# 2021.net
KiCad netlist of a schematic drawn in EasyEDA Pro
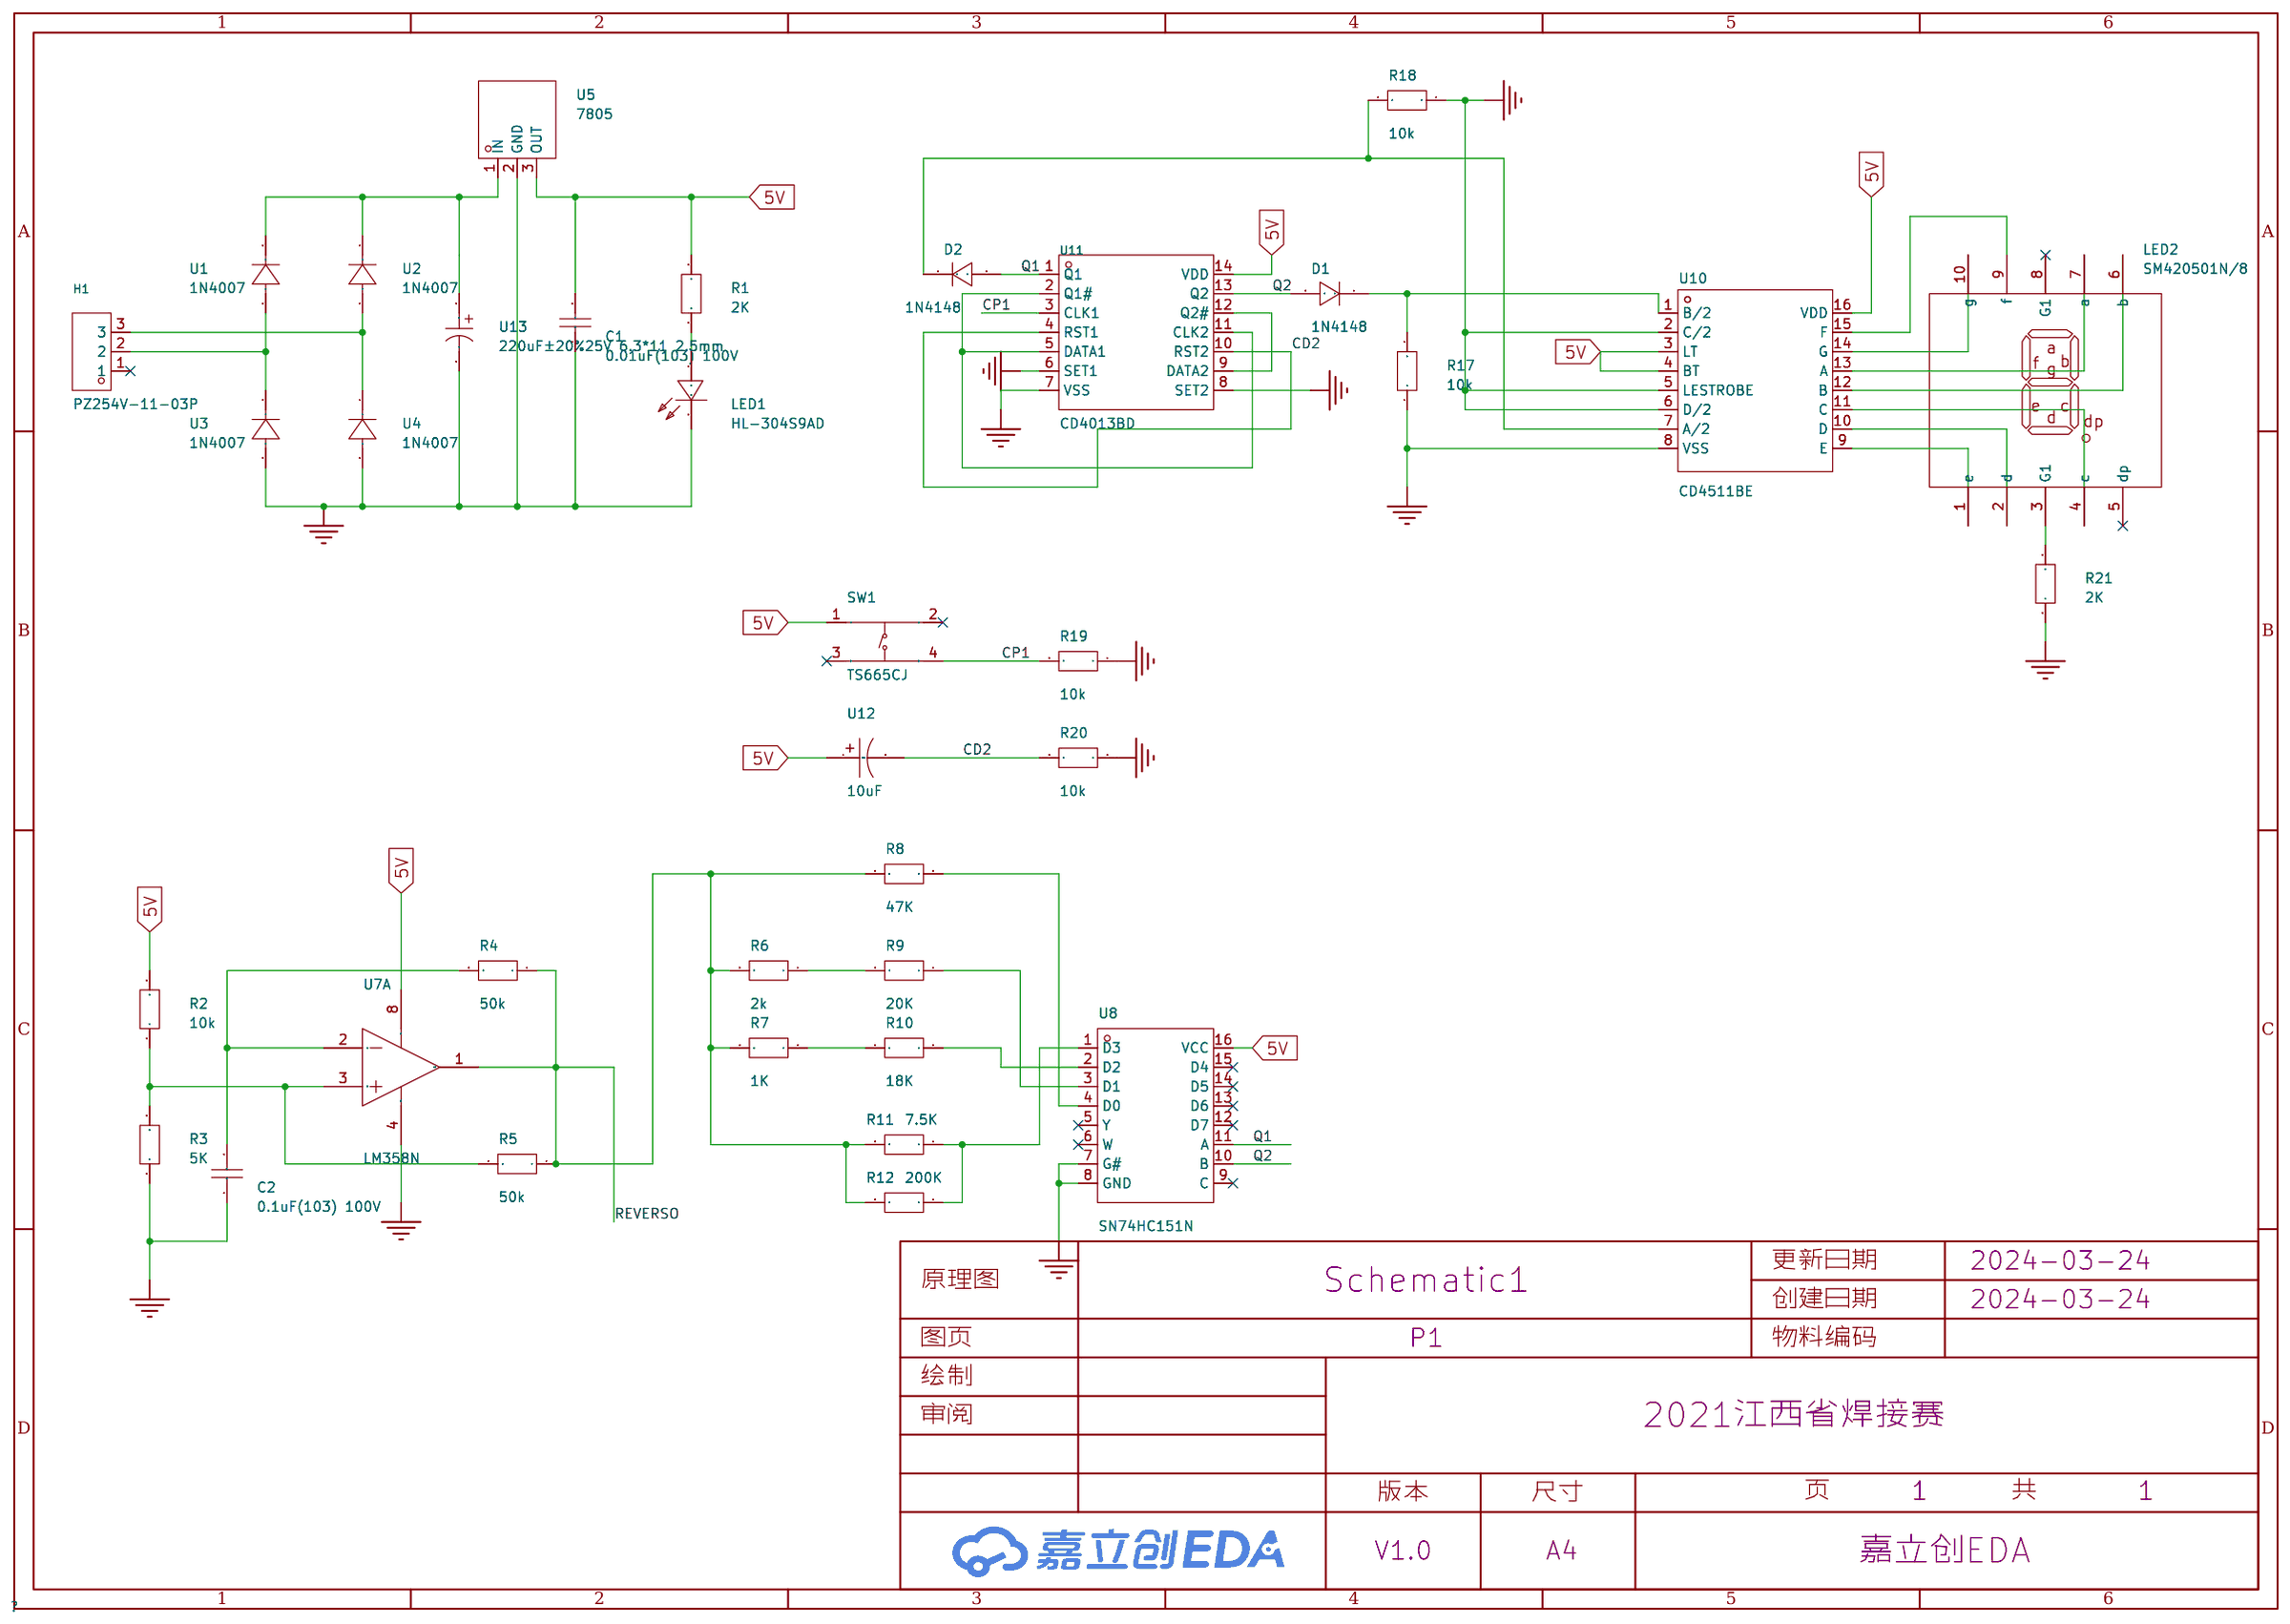
[diagram p0: schematic sheet]

(export (version "E")
  (design (tool "Eeschema 10.0.6"))
  (components
    (comp (ref "C1")
      (value "0.01uF(103) 100V")
      (footprint "easyedapro:CAP-TH_L5.5-W3.0-P5.00-D0.5")
      (libsource (lib "easyedapro") (part "0.01uF(103) 100V"))
    )
    (comp (ref "C2")
      (value "0.1uF(103) 100V")
      (footprint "easyedapro:CAP-TH_L5.5-W3.0-P5.00-D0.5")
      (libsource (lib "easyedapro") (part "0.01uF(103) 100V"))
    )
    (comp (ref "D1")
      (value "1N4148")
      (footprint "easyedapro:DO-35_BD2.0-L4.0-P8.0-D0.5-RD")
      (description "二极管配置:-;正向压降(Vf):-;直流反向耐压(Vr):-;平均整流电流(Io):-;")
      (libsource (lib "easyedapro") (part "1N4148_C13769"))
    )
    (comp (ref "D2")
      (value "1N4148")
      (footprint "easyedapro:DO-35_BD2.0-L4.0-P8.0-D0.5-RD")
      (description "二极管配置:-;正向压降(Vf):-;直流反向耐压(Vr):-;平均整流电流(Io):-;")
      (libsource (lib "easyedapro") (part "1N4148_C13769"))
    )
    (comp (ref "H1")
      (value "PZ254V-11-03P")
      (footprint "easyedapro:HDR-TH_3P-P2.54-V-M")
      (fields (field (name "Manufacturer") "XFCN(兴飞)"))
      (libsource (lib "easyedapro") (part "PZ254V-11-03P_C2937625"))
    )
    (comp (ref "LED1")
      (value "HL-304S9AD")
      (footprint "easyedapro:LED-TH_BD3.0-P2.54-FD")
      (fields (field (name "Manufacturer") "HONGLITRONIC(鸿利光电)"))
      (libsource (lib "easyedapro") (part "HL-304S9AD"))
    )
    (comp (ref "LED2")
      (value "SM420501N/8")
      (footprint "easyedapro:LED-SEG-TH_10P-L12.7-W19.0-P2.54-S15.24-BL")
      (description "数码管位数:1位;发光颜色:红色;LED极性:共阴极;数字/字母大小(英寸):0.5;")
      (fields (field (name "Manufacturer") "ARKLED(方舟)"))
      (libsource (lib "easyedapro") (part "SM420501N/8"))
    )
    (comp (ref "R1")
      (value "2K")
      (footprint "easyedapro:RES-TH_BD2.3-L6.5-P10.50-D0.5")
      (description "电阻类型:金属膜电阻;阻值:1kΩ;精度:±1%;功率:250mW;温度系数:±200ppm/°C;")
      (fields (field (name "Manufacturer Part") "MF1/4W-1KΩ±1%T52") (field (name "Manufacturer") "华星机电"))
      (libsource (lib "easyedapro") (part "MF1/4W-1KΩ±1%T52"))
    )
    (comp (ref "R2")
      (value "10k")
      (footprint "easyedapro:RES-TH_BD2.3-L6.5-P10.50-D0.5")
      (description "电阻类型:金属膜电阻;阻值:1kΩ;精度:±1%;功率:250mW;温度系数:±200ppm/°C;")
      (fields (field (name "Manufacturer Part") "MF1/4W-1KΩ±1%T52") (field (name "Manufacturer") "华星机电"))
      (libsource (lib "easyedapro") (part "MF1/4W-1KΩ±1%T52"))
    )
    (comp (ref "R3")
      (value "5K")
      (footprint "easyedapro:RES-TH_BD2.3-L6.5-P10.50-D0.5")
      (description "电阻类型:金属膜电阻;阻值:1kΩ;精度:±1%;功率:250mW;温度系数:±200ppm/°C;")
      (fields (field (name "Manufacturer Part") "MF1/4W-1KΩ±1%T52") (field (name "Manufacturer") "华星机电"))
      (libsource (lib "easyedapro") (part "MF1/4W-1KΩ±1%T52"))
    )
    (comp (ref "R4")
      (value "50k")
      (footprint "easyedapro:RES-TH_BD2.3-L6.5-P10.50-D0.5")
      (description "电阻类型:金属膜电阻;阻值:1kΩ;精度:±1%;功率:250mW;温度系数:±200ppm/°C;")
      (fields (field (name "Manufacturer Part") "MF1/4W-1KΩ±1%T52") (field (name "Manufacturer") "华星机电"))
      (libsource (lib "easyedapro") (part "MF1/4W-1KΩ±1%T52"))
    )
    (comp (ref "R5")
      (value "50k")
      (footprint "easyedapro:RES-TH_BD2.3-L6.5-P10.50-D0.5")
      (description "电阻类型:金属膜电阻;阻值:1kΩ;精度:±1%;功率:250mW;温度系数:±200ppm/°C;")
      (fields (field (name "Manufacturer Part") "MF1/4W-1KΩ±1%T52") (field (name "Manufacturer") "华星机电"))
      (libsource (lib "easyedapro") (part "MF1/4W-1KΩ±1%T52"))
    )
    (comp (ref "R6")
      (value "2k")
      (footprint "easyedapro:RES-TH_BD2.3-L6.5-P10.50-D0.5")
      (description "电阻类型:金属膜电阻;阻值:1kΩ;精度:±1%;功率:250mW;温度系数:±200ppm/°C;")
      (fields (field (name "Manufacturer Part") "MF1/4W-1KΩ±1%T52") (field (name "Manufacturer") "华星机电"))
      (libsource (lib "easyedapro") (part "MF1/4W-1KΩ±1%T52"))
    )
    (comp (ref "R7")
      (value "1K")
      (footprint "easyedapro:RES-TH_BD2.3-L6.5-P10.50-D0.5")
      (description "电阻类型:金属膜电阻;阻值:1kΩ;精度:±1%;功率:250mW;温度系数:±200ppm/°C;")
      (fields (field (name "Manufacturer Part") "MF1/4W-1KΩ±1%T52") (field (name "Manufacturer") "华星机电"))
      (libsource (lib "easyedapro") (part "MF1/4W-1KΩ±1%T52"))
    )
    (comp (ref "R8")
      (value "47K")
      (footprint "easyedapro:RES-TH_BD2.3-L6.5-P10.50-D0.5")
      (description "电阻类型:金属膜电阻;阻值:1kΩ;精度:±1%;功率:250mW;温度系数:±200ppm/°C;")
      (fields (field (name "Manufacturer Part") "MF1/4W-1KΩ±1%T52") (field (name "Manufacturer") "华星机电"))
      (libsource (lib "easyedapro") (part "MF1/4W-1KΩ±1%T52"))
    )
    (comp (ref "R9")
      (value "20K")
      (footprint "easyedapro:RES-TH_BD2.3-L6.5-P10.50-D0.5")
      (description "电阻类型:金属膜电阻;阻值:1kΩ;精度:±1%;功率:250mW;温度系数:±200ppm/°C;")
      (fields (field (name "Manufacturer Part") "MF1/4W-1KΩ±1%T52") (field (name "Manufacturer") "华星机电"))
      (libsource (lib "easyedapro") (part "MF1/4W-1KΩ±1%T52"))
    )
    (comp (ref "R10")
      (value "18K")
      (footprint "easyedapro:RES-TH_BD2.3-L6.5-P10.50-D0.5")
      (description "电阻类型:金属膜电阻;阻值:1kΩ;精度:±1%;功率:250mW;温度系数:±200ppm/°C;")
      (fields (field (name "Manufacturer Part") "MF1/4W-1KΩ±1%T52") (field (name "Manufacturer") "华星机电"))
      (libsource (lib "easyedapro") (part "MF1/4W-1KΩ±1%T52"))
    )
    (comp (ref "R11")
      (value "7.5K")
      (footprint "easyedapro:RES-TH_BD2.3-L6.5-P10.50-D0.5")
      (description "电阻类型:金属膜电阻;阻值:1kΩ;精度:±1%;功率:250mW;温度系数:±200ppm/°C;")
      (fields (field (name "Manufacturer Part") "MF1/4W-1KΩ±1%T52") (field (name "Manufacturer") "华星机电"))
      (libsource (lib "easyedapro") (part "MF1/4W-1KΩ±1%T52"))
    )
    (comp (ref "R12")
      (value "200K")
      (footprint "easyedapro:RES-TH_BD2.3-L6.5-P10.50-D0.5")
      (description "电阻类型:金属膜电阻;阻值:1kΩ;精度:±1%;功率:250mW;温度系数:±200ppm/°C;")
      (fields (field (name "Manufacturer Part") "MF1/4W-1KΩ±1%T52") (field (name "Manufacturer") "华星机电"))
      (libsource (lib "easyedapro") (part "MF1/4W-1KΩ±1%T52"))
    )
    (comp (ref "R17")
      (value "10k")
      (footprint "easyedapro:RES-TH_BD2.3-L6.5-P10.50-D0.5")
      (description "电阻类型:金属膜电阻;阻值:1kΩ;精度:±1%;功率:250mW;温度系数:±200ppm/°C;")
      (fields (field (name "Manufacturer Part") "MF1/4W-1KΩ±1%T52") (field (name "Manufacturer") "华星机电"))
      (libsource (lib "easyedapro") (part "MF1/4W-1KΩ±1%T52"))
    )
    (comp (ref "R18")
      (value "10k")
      (footprint "easyedapro:RES-TH_BD2.3-L6.5-P10.50-D0.5")
      (description "电阻类型:金属膜电阻;阻值:1kΩ;精度:±1%;功率:250mW;温度系数:±200ppm/°C;")
      (fields (field (name "Manufacturer Part") "MF1/4W-1KΩ±1%T52") (field (name "Manufacturer") "华星机电"))
      (libsource (lib "easyedapro") (part "MF1/4W-1KΩ±1%T52"))
    )
    (comp (ref "R19")
      (value "10k")
      (footprint "easyedapro:RES-TH_BD2.3-L6.5-P10.50-D0.5")
      (description "电阻类型:金属膜电阻;阻值:1kΩ;精度:±1%;功率:250mW;温度系数:±200ppm/°C;")
      (fields (field (name "Manufacturer Part") "MF1/4W-1KΩ±1%T52") (field (name "Manufacturer") "华星机电"))
      (libsource (lib "easyedapro") (part "MF1/4W-1KΩ±1%T52"))
    )
    (comp (ref "R20")
      (value "10k")
      (footprint "easyedapro:RES-TH_BD2.3-L6.5-P10.50-D0.5")
      (description "电阻类型:金属膜电阻;阻值:1kΩ;精度:±1%;功率:250mW;温度系数:±200ppm/°C;")
      (fields (field (name "Manufacturer Part") "MF1/4W-1KΩ±1%T52") (field (name "Manufacturer") "华星机电"))
      (libsource (lib "easyedapro") (part "MF1/4W-1KΩ±1%T52"))
    )
    (comp (ref "R21")
      (value "2K")
      (footprint "easyedapro:RES-TH_BD2.3-L6.5-P10.50-D0.5")
      (description "电阻类型:金属膜电阻;阻值:1kΩ;精度:±1%;功率:250mW;温度系数:±200ppm/°C;")
      (fields (field (name "Manufacturer Part") "MF1/4W-1KΩ±1%T52") (field (name "Manufacturer") "华星机电"))
      (libsource (lib "easyedapro") (part "MF1/4W-1KΩ±1%T52"))
    )
    (comp (ref "SW1")
      (value "TS665CJ")
      (footprint "easyedapro:SW-TH_4P-L6.0-W6.0-P4.50-LS6.5")
      (description "电路结构:单刀单掷;按钮形状:圆形按钮;安装方式:直插;开关长度:6mm;开关宽度:6mm;开关高度:5mm;触点电流:50mA;额定电压(DC):12V;带灯:-;机械寿命:-;")
      (fields (field (name "Manufacturer") "SHOU HAN(首韩)"))
      (libsource (lib "easyedapro") (part "TS665CJ"))
    )
    (comp (ref "U1")
      (value "1N4007")
      (footprint "easyedapro:DO-41_BD2.8-L5.2-P9.20-D0.8-RD")
      (fields (field (name "Manufacturer") "Zhengxin(正芯)"))
      (libsource (lib "easyedapro") (part "1N4007_C19272205"))
    )
    (comp (ref "U2")
      (value "1N4007")
      (footprint "easyedapro:DO-41_BD2.8-L5.2-P9.20-D0.8-RD")
      (fields (field (name "Manufacturer") "Zhengxin(正芯)"))
      (libsource (lib "easyedapro") (part "1N4007_C19272205"))
    )
    (comp (ref "U3")
      (value "1N4007")
      (footprint "easyedapro:DO-41_BD2.8-L5.2-P9.20-D0.8-RD")
      (fields (field (name "Manufacturer") "Zhengxin(正芯)"))
      (libsource (lib "easyedapro") (part "1N4007_C19272205"))
    )
    (comp (ref "U4")
      (value "1N4007")
      (footprint "easyedapro:DO-41_BD2.8-L5.2-P9.20-D0.8-RD")
      (fields (field (name "Manufacturer") "Zhengxin(正芯)"))
      (libsource (lib "easyedapro") (part "1N4007_C19272205"))
    )
    (comp (ref "U5")
      (value "7805")
      (footprint "easyedapro:TO-220-3_L10.2-W4.5-P2.54-L-1")
      (description "输出类型:固定;最大输入电压:35V;输出电压:5V;最大输出电流:1.5A;电源纹波抑制比(PSRR):62dB@(120Hz);输出极性:正极;")
      (fields (field (name "Manufacturer") "SY(顺烨）"))
      (libsource (lib "easyedapro") (part "7805_C4944936"))
    )
    (comp (ref "U7")
      (value "LM358N")
      (footprint "easyedapro:DIP-8_L9.2-W6.3-P2.54-LS7.62-BL")
      (description "放大器数:-;")
      (fields (field (name "Manufacturer") "HGSEMI(华冠)"))
      (libsource (lib "easyedapro") (part "LM358N_C434570"))
    )
    (comp (ref "U8")
      (value "SN74HC151N")
      (footprint "easyedapro:PDIP-16_L19.7-W6.6-P2.54-LS7.8-BL")
      (description "供电电压:2V~6V;灌电流(IOL):7.8mA;拉电流(IOH):7.8mA;")
      (fields (field (name "Manufacturer") "TI(德州仪器)"))
      (libsource (lib "easyedapro") (part "SN74HC151N"))
    )
    (comp (ref "U10")
      (value "CD4511BE")
      (footprint "easyedapro:DIP-16_L19.8-W6.5-P2.54-LS7.6-BL")
      (description "CD4511B CMOS BCD 到 7 段 LED 锁存解码器驱动器")
      (fields (field (name "Manufacturer") "TI(德州仪器)"))
      (libsource (lib "easyedapro") (part "CD4511BE"))
    )
    (comp (ref "U11")
      (value "CD4013BD")
      (footprint "easyedapro:DIP-14_L19.6-W6.4-P2.54-LS7.6-BL")
      (description "类型:D-型;")
      (fields (field (name "Manufacturer") "Sungine(双竞集成)"))
      (libsource (lib "easyedapro") (part "CD4013BD"))
    )
    (comp (ref "U12")
      (value "10uF")
      (footprint "easyedapro:CAP-TH_BD6.3-P2.50-D0.5-FD")
      (description "容值:10uF;精度:±20%;额定电压:400V;纹波电流:-;等效串联电阻:-;")
      (fields
        (field (name "Manufacturer Part") "MHT10UF400V87EC0217")
        (field (name "Manufacturer") "KNSCHA(科尼盛)")
      )
      (libsource (lib "easyedapro") (part "MHT10UF400V87EC0217"))
    )
    (comp (ref "U13")
      (value "220uF±20%25V 6.3*11 2.5mm")
      (footprint "easyedapro:CAP-TH_BD6.3-P2.50-D0.5-FD")
      (libsource (lib "easyedapro") (part "220UF±20%25V 6.3*11 2.5MM"))
    )
  )
  (nets
    (net (code "1") (name "/CD2") (class "Default")
      (node (ref "R20") (pin "2") (pinfunction "2_2") (pintype "unspecified"))
      (node (ref "U11") (pin "10") (pinfunction "RST2_10") (pintype "input"))
      (node (ref "U11") (pin "4") (pinfunction "RST1_4") (pintype "input"))
      (node (ref "U12") (pin "2") (pinfunction "2_2") (pintype "unspecified"))
    )
    (net (code "2") (name "/CP1") (class "Default")
      (node (ref "R19") (pin "2") (pinfunction "2_2") (pintype "unspecified"))
      (node (ref "SW1") (pin "4") (pinfunction "D_4") (pintype "unspecified"))
      (node (ref "U11") (pin "3") (pinfunction "CLK1_3") (pintype "input"))
    )
    (net (code "3") (name "/Q1") (class "Default")
      (node (ref "D2") (pin "2") (pinfunction "2_2") (pintype "unspecified"))
      (node (ref "U11") (pin "1") (pinfunction "Q1_1") (pintype "input"))
      (node (ref "U8") (pin "11") (pinfunction "A_11") (pintype "unspecified"))
    )
    (net (code "4") (name "/Q2") (class "Default")
      (node (ref "D1") (pin "2") (pinfunction "2_2") (pintype "unspecified"))
      (node (ref "U11") (pin "13") (pinfunction "Q2_13") (pintype "input"))
      (node (ref "U8") (pin "10") (pinfunction "B_10") (pintype "unspecified"))
    )
    (net (code "5") (name "/REVERSO") (class "Default")
      (node (ref "R11") (pin "2") (pinfunction "2_2") (pintype "unspecified"))
      (node (ref "R12") (pin "2") (pinfunction "2_2") (pintype "unspecified"))
      (node (ref "R4") (pin "1") (pinfunction "1_1") (pintype "unspecified"))
      (node (ref "R5") (pin "1") (pinfunction "1_1") (pintype "unspecified"))
      (node (ref "R6") (pin "2") (pinfunction "2_2") (pintype "unspecified"))
      (node (ref "R7") (pin "2") (pinfunction "2_2") (pintype "unspecified"))
      (node (ref "R8") (pin "2") (pinfunction "2_2") (pintype "unspecified"))
      (node (ref "U7") (pin "1") (pinfunction "OUT1_1") (pintype "output"))
    )
    (net (code "6") (name "5V") (class "Default")
      (node (ref "C1") (pin "2") (pinfunction "2_2") (pintype "input"))
      (node (ref "R1") (pin "2") (pinfunction "2_2") (pintype "unspecified"))
      (node (ref "R2") (pin "2") (pinfunction "2_2") (pintype "unspecified"))
      (node (ref "SW1") (pin "1") (pinfunction "A_1") (pintype "unspecified"))
      (node (ref "U10") (pin "16") (pinfunction "VDD_16") (pintype "input"))
      (node (ref "U10") (pin "3") (pinfunction "LT_3") (pintype "input"))
      (node (ref "U10") (pin "4") (pinfunction "BT_4") (pintype "input"))
      (node (ref "U11") (pin "14") (pinfunction "VDD_14") (pintype "input"))
      (node (ref "U12") (pin "1") (pinfunction "1_1") (pintype "unspecified"))
      (node (ref "U5") (pin "3") (pinfunction "OUT_3") (pintype "unspecified"))
      (node (ref "U7") (pin "8") (pinfunction "VCC_8") (pintype "unspecified"))
      (node (ref "U8") (pin "16") (pinfunction "VCC_16") (pintype "unspecified"))
    )
    (net (code "7") (name "GND") (class "Default")
      (node (ref "C1") (pin "1") (pinfunction "1_1") (pintype "input"))
      (node (ref "C2") (pin "1") (pinfunction "1_1") (pintype "input"))
      (node (ref "LED1") (pin "2") (pinfunction "C_2") (pintype "unspecified"))
      (node (ref "R17") (pin "1") (pinfunction "1_1") (pintype "unspecified"))
      (node (ref "R18") (pin "1") (pinfunction "1_1") (pintype "unspecified"))
      (node (ref "R19") (pin "1") (pinfunction "1_1") (pintype "unspecified"))
      (node (ref "R20") (pin "1") (pinfunction "1_1") (pintype "unspecified"))
      (node (ref "R21") (pin "1") (pinfunction "1_1") (pintype "unspecified"))
      (node (ref "R3") (pin "1") (pinfunction "1_1") (pintype "unspecified"))
      (node (ref "U10") (pin "2") (pinfunction "C/2_2") (pintype "input"))
      (node (ref "U10") (pin "5") (pinfunction "LESTROBE_5") (pintype "input"))
      (node (ref "U10") (pin "6") (pinfunction "D/2_6") (pintype "input"))
      (node (ref "U10") (pin "8") (pinfunction "VSS_8") (pintype "input"))
      (node (ref "U11") (pin "6") (pinfunction "SET1_6") (pintype "input"))
      (node (ref "U11") (pin "7") (pinfunction "VSS_7") (pintype "input"))
      (node (ref "U11") (pin "8") (pinfunction "SET2_8") (pintype "input"))
      (node (ref "U13") (pin "2") (pinfunction "2_2") (pintype "input"))
      (node (ref "U3") (pin "2") (pinfunction "A_2") (pintype "unspecified"))
      (node (ref "U4") (pin "2") (pinfunction "A_2") (pintype "unspecified"))
      (node (ref "U5") (pin "2") (pinfunction "GND_2") (pintype "unspecified"))
      (node (ref "U7") (pin "4") (pinfunction "GND_4") (pintype "unspecified"))
      (node (ref "U8") (pin "7") (pinfunction "G#_7") (pintype "unspecified"))
      (node (ref "U8") (pin "8") (pinfunction "GND_8") (pintype "unspecified"))
    )
    (net (code "8") (name "Net-(LED1-A)") (class "Default")
      (node (ref "LED1") (pin "1") (pinfunction "A_1") (pintype "unspecified"))
      (node (ref "R1") (pin "1") (pinfunction "1_1") (pintype "unspecified"))
    )
    (net (code "9") (name "Net-(LED2-G1-Pad3)") (class "Default")
      (node (ref "LED2") (pin "3") (pinfunction "G1_3") (pintype "input"))
      (node (ref "R21") (pin "2") (pinfunction "2_2") (pintype "unspecified"))
    )
    (net (code "10") (name "Net-(LED2-a)") (class "Default")
      (node (ref "LED2") (pin "7") (pinfunction "a_7") (pintype "input"))
      (node (ref "U10") (pin "13") (pinfunction "A_13") (pintype "input"))
    )
    (net (code "11") (name "Net-(LED2-b)") (class "Default")
      (node (ref "LED2") (pin "6") (pinfunction "b_6") (pintype "input"))
      (node (ref "U10") (pin "12") (pinfunction "B_12") (pintype "input"))
    )
    (net (code "12") (name "Net-(LED2-c)") (class "Default")
      (node (ref "LED2") (pin "4") (pinfunction "c_4") (pintype "input"))
      (node (ref "U10") (pin "11") (pinfunction "C_11") (pintype "input"))
    )
    (net (code "13") (name "Net-(LED2-d)") (class "Default")
      (node (ref "LED2") (pin "2") (pinfunction "d_2") (pintype "input"))
      (node (ref "U10") (pin "10") (pinfunction "D_10") (pintype "input"))
    )
    (net (code "14") (name "Net-(LED2-e)") (class "Default")
      (node (ref "LED2") (pin "1") (pinfunction "e_1") (pintype "input"))
      (node (ref "U10") (pin "9") (pinfunction "E_9") (pintype "input"))
    )
    (net (code "15") (name "Net-(LED2-f)") (class "Default")
      (node (ref "LED2") (pin "9") (pinfunction "f_9") (pintype "input"))
      (node (ref "U10") (pin "15") (pinfunction "F_15") (pintype "input"))
    )
    (net (code "16") (name "Net-(LED2-g)") (class "Default")
      (node (ref "LED2") (pin "10") (pinfunction "g_10") (pintype "input"))
      (node (ref "U10") (pin "14") (pinfunction "G_14") (pintype "input"))
    )
    (net (code "17") (name "Net-(R6-Pad1)") (class "Default")
      (node (ref "R6") (pin "1") (pinfunction "1_1") (pintype "unspecified"))
      (node (ref "R9") (pin "2") (pinfunction "2_2") (pintype "unspecified"))
    )
    (net (code "18") (name "Net-(R10-Pad2)") (class "Default")
      (node (ref "R10") (pin "2") (pinfunction "2_2") (pintype "unspecified"))
      (node (ref "R7") (pin "1") (pinfunction "1_1") (pintype "unspecified"))
    )
    (net (code "19") (name "Net-(U1-A)") (class "Default")
      (node (ref "H1") (pin "2") (pinfunction "2_2") (pintype "input"))
      (node (ref "U1") (pin "2") (pinfunction "A_2") (pintype "unspecified"))
      (node (ref "U3") (pin "1") (pinfunction "K_1") (pintype "unspecified"))
    )
    (net (code "20") (name "Net-(U1-K)") (class "Default")
      (node (ref "U1") (pin "1") (pinfunction "K_1") (pintype "unspecified"))
      (node (ref "U13") (pin "1") (pinfunction "1_1") (pintype "input"))
      (node (ref "U2") (pin "1") (pinfunction "K_1") (pintype "unspecified"))
      (node (ref "U5") (pin "1") (pinfunction "IN_1") (pintype "unspecified"))
    )
    (net (code "21") (name "Net-(U2-A)") (class "Default")
      (node (ref "H1") (pin "3") (pinfunction "3_3") (pintype "input"))
      (node (ref "U2") (pin "2") (pinfunction "A_2") (pintype "unspecified"))
      (node (ref "U4") (pin "1") (pinfunction "K_1") (pintype "unspecified"))
    )
    (net (code "22") (name "Net-(U7A-IN1+)") (class "Default")
      (node (ref "R2") (pin "1") (pinfunction "1_1") (pintype "unspecified"))
      (node (ref "R3") (pin "2") (pinfunction "2_2") (pintype "unspecified"))
      (node (ref "R5") (pin "2") (pinfunction "2_2") (pintype "unspecified"))
      (node (ref "U7") (pin "3") (pinfunction "IN1+_3") (pintype "unspecified"))
    )
    (net (code "23") (name "Net-(U7A-IN1-)") (class "Default")
      (node (ref "C2") (pin "2") (pinfunction "2_2") (pintype "input"))
      (node (ref "R4") (pin "2") (pinfunction "2_2") (pintype "unspecified"))
      (node (ref "U7") (pin "2") (pinfunction "IN1-_2") (pintype "unspecified"))
    )
    (net (code "24") (name "Net-(U8-D0)") (class "Default")
      (node (ref "R8") (pin "1") (pinfunction "1_1") (pintype "unspecified"))
      (node (ref "U8") (pin "4") (pinfunction "D0_4") (pintype "unspecified"))
    )
    (net (code "25") (name "Net-(U8-D1)") (class "Default")
      (node (ref "R9") (pin "1") (pinfunction "1_1") (pintype "unspecified"))
      (node (ref "U8") (pin "3") (pinfunction "D1_3") (pintype "unspecified"))
    )
    (net (code "26") (name "Net-(U8-D2)") (class "Default")
      (node (ref "R10") (pin "1") (pinfunction "1_1") (pintype "unspecified"))
      (node (ref "U8") (pin "2") (pinfunction "D2_2") (pintype "unspecified"))
    )
    (net (code "27") (name "Net-(U8-D3)") (class "Default")
      (node (ref "R11") (pin "1") (pinfunction "1_1") (pintype "unspecified"))
      (node (ref "R12") (pin "1") (pinfunction "1_1") (pintype "unspecified"))
      (node (ref "U8") (pin "1") (pinfunction "D3_1") (pintype "unspecified"))
    )
    (net (code "28") (name "Net-(U10-A{slash}2)") (class "Default")
      (node (ref "D2") (pin "1") (pinfunction "1_1") (pintype "unspecified"))
      (node (ref "R18") (pin "2") (pinfunction "2_2") (pintype "unspecified"))
      (node (ref "U10") (pin "7") (pinfunction "A/2_7") (pintype "input"))
    )
    (net (code "29") (name "Net-(U10-B{slash}2)") (class "Default")
      (node (ref "D1") (pin "1") (pinfunction "1_1") (pintype "unspecified"))
      (node (ref "R17") (pin "2") (pinfunction "2_2") (pintype "unspecified"))
      (node (ref "U10") (pin "1") (pinfunction "B/2_1") (pintype "input"))
    )
    (net (code "30") (name "Net-(U11-CLK2)") (class "Default")
      (node (ref "U11") (pin "11") (pinfunction "CLK2_11") (pintype "input"))
      (node (ref "U11") (pin "2") (pinfunction "Q1#_2") (pintype "input"))
      (node (ref "U11") (pin "5") (pinfunction "DATA1_5") (pintype "input"))
    )
    (net (code "31") (name "Net-(U11-DATA2)") (class "Default")
      (node (ref "U11") (pin "12") (pinfunction "Q2#_12") (pintype "input"))
      (node (ref "U11") (pin "9") (pinfunction "DATA2_9") (pintype "input"))
    )
    (net (code "32") (name "unconnected-(H1-Pad1)") (class "Default")
      (node (ref "H1") (pin "1") (pinfunction "1_1") (pintype "input+no_connect"))
    )
    (net (code "33") (name "unconnected-(LED2-G1-Pad8)") (class "Default")
      (node (ref "LED2") (pin "8") (pinfunction "G1_8") (pintype "input+no_connect"))
    )
    (net (code "34") (name "unconnected-(LED2-dp-Pad5)") (class "Default")
      (node (ref "LED2") (pin "5") (pinfunction "dp_5") (pintype "input+no_connect"))
    )
    (net (code "35") (name "unconnected-(SW1-B-Pad2)") (class "Default")
      (node (ref "SW1") (pin "2") (pinfunction "B_2") (pintype "unspecified+no_connect"))
    )
    (net (code "36") (name "unconnected-(SW1-C-Pad3)") (class "Default")
      (node (ref "SW1") (pin "3") (pinfunction "C_3") (pintype "unspecified+no_connect"))
    )
    (net (code "37") (name "unconnected-(U8-C-Pad9)") (class "Default")
      (node (ref "U8") (pin "9") (pinfunction "C_9") (pintype "unspecified+no_connect"))
    )
    (net (code "38") (name "unconnected-(U8-D4-Pad15)") (class "Default")
      (node (ref "U8") (pin "15") (pinfunction "D4_15") (pintype "unspecified+no_connect"))
    )
    (net (code "39") (name "unconnected-(U8-D5-Pad14)") (class "Default")
      (node (ref "U8") (pin "14") (pinfunction "D5_14") (pintype "unspecified+no_connect"))
    )
    (net (code "40") (name "unconnected-(U8-D6-Pad13)") (class "Default")
      (node (ref "U8") (pin "13") (pinfunction "D6_13") (pintype "unspecified+no_connect"))
    )
    (net (code "41") (name "unconnected-(U8-D7-Pad12)") (class "Default")
      (node (ref "U8") (pin "12") (pinfunction "D7_12") (pintype "unspecified+no_connect"))
    )
    (net (code "42") (name "unconnected-(U8-W-Pad6)") (class "Default")
      (node (ref "U8") (pin "6") (pinfunction "W_6") (pintype "unspecified+no_connect"))
    )
    (net (code "43") (name "unconnected-(U8-Y-Pad5)") (class "Default")
      (node (ref "U8") (pin "5") (pinfunction "Y_5") (pintype "unspecified+no_connect"))
    )
  )
)
